# DC-PSx.net
KiCad netlist of a schematic drawn in EAGLE
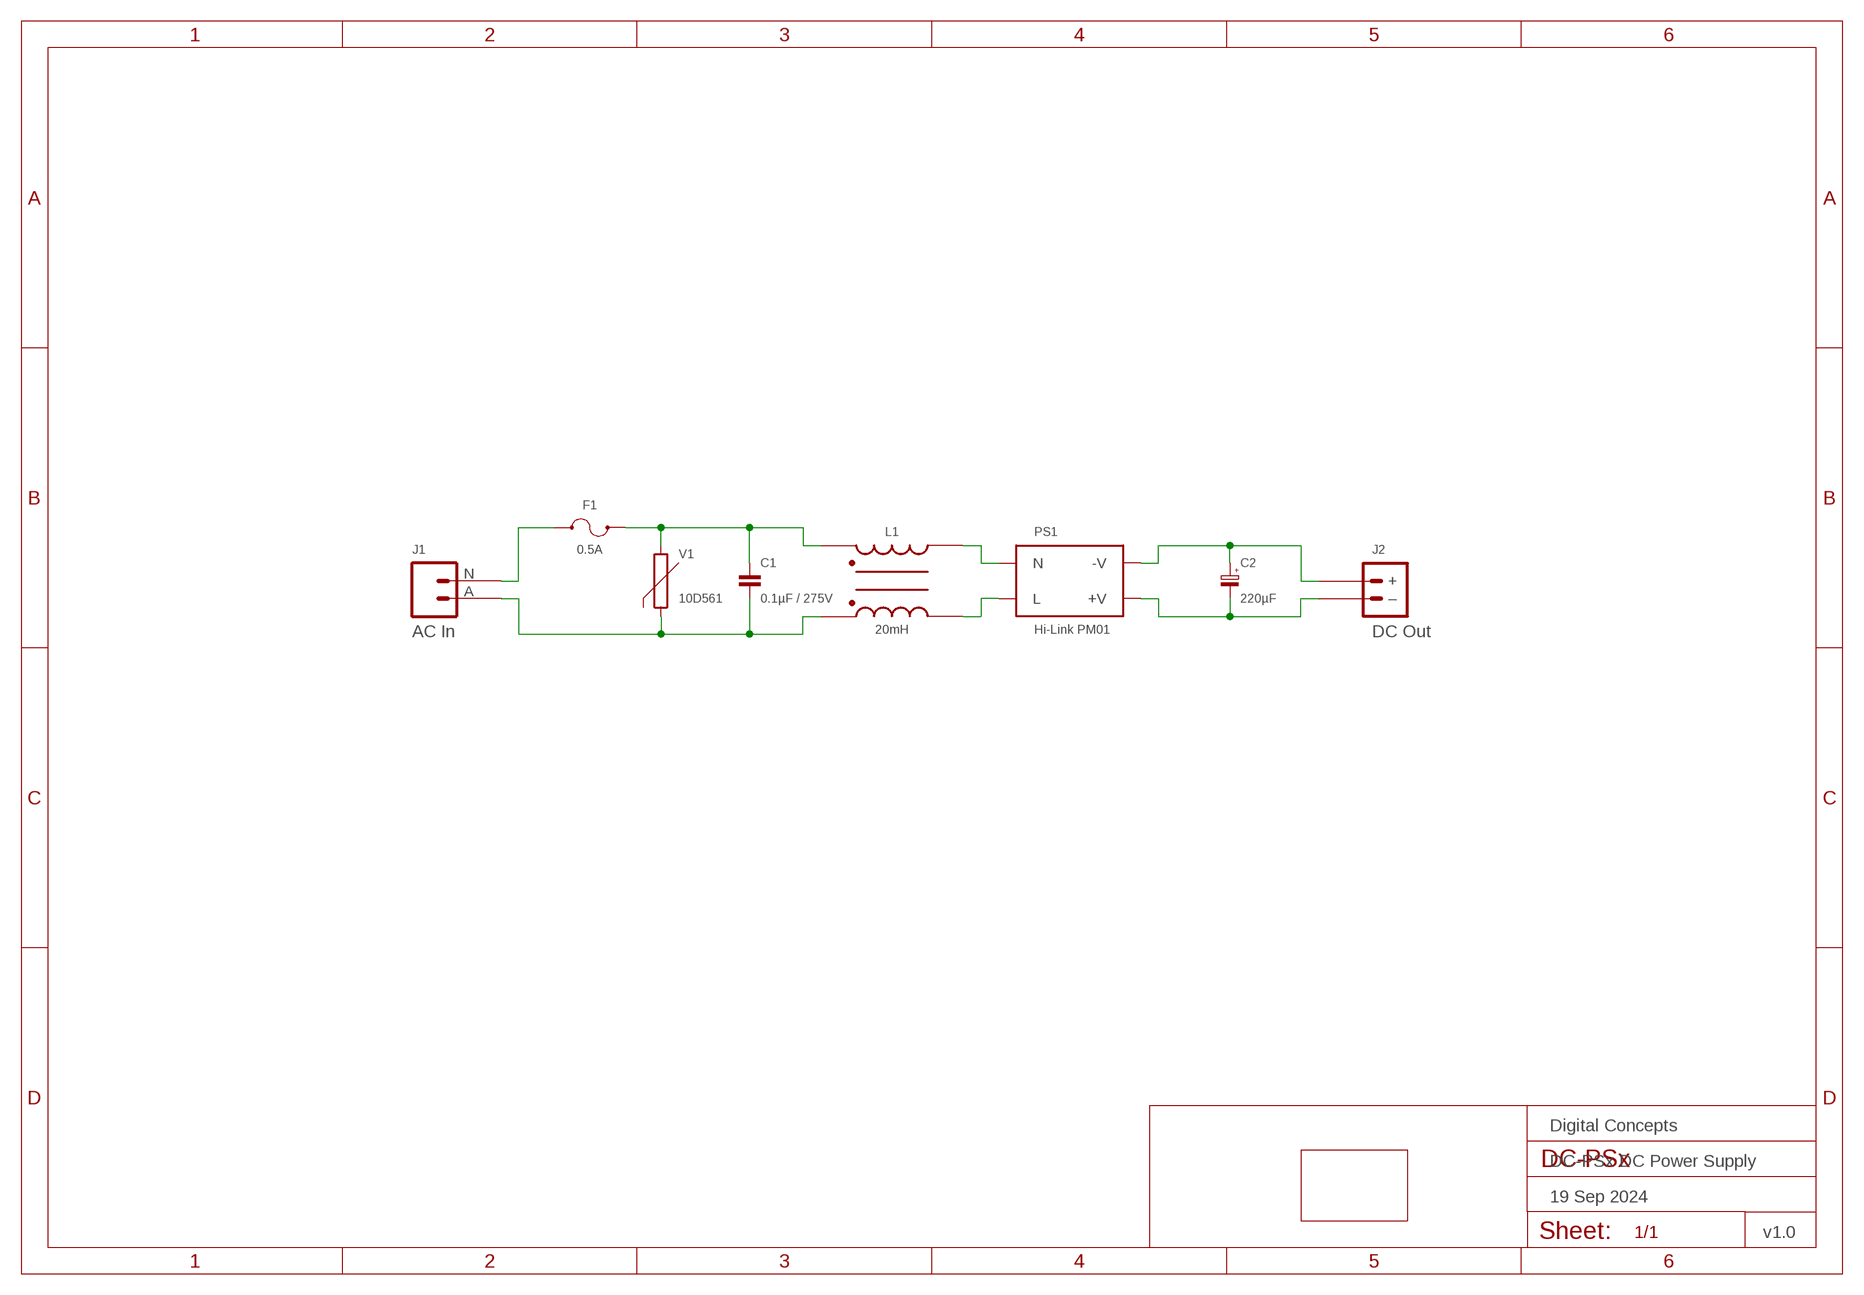
[diagram p0: schematic, sheet 1]

(export (version "E")
  (design (tool "Eeschema 10.0.6"))
  (components
    (comp (ref "C1")
      (value "0.1µF / 275V")
      (footprint "eagle-import:CAPACITOR-TENTA-SUPPRESSION")
      (libsource (lib "eagle-import") (part "CAPACITOR-TENTA-SUPPRESSION"))
    )
    (comp (ref "C2")
      (value "220µF")
      (footprint "eagle-import:E5-10,5")
      (libsource (lib "eagle-import") (part "CAPACITOR-ELECTROLYTICE5-10.5"))
    )
    (comp (ref "F1")
      (value "0.5A")
      (footprint "eagle-import:FUSE-HOLDER-1808")
      (libsource (lib "eagle-import") (part "FUSE-HOLDER-1808"))
    )
    (comp (ref "J1")
      (value "AC In")
      (footprint "eagle-import:DB-03_AC_POWER_SOCKET")
      (libsource (lib "eagle-import") (part "AC_POWER_SOCKET_DB-03"))
    )
    (comp (ref "J2")
      (value "DC Out")
      (footprint "eagle-import:JST-PH2.0-2-VERTICAL-POWER")
      (libsource (lib "eagle-import") (part "JST-PH2.0-2-VERTICAL-POWER"))
    )
    (comp (ref "L1")
      (value "20mH")
      (footprint "eagle-import:INDUCTOR-UU9.8")
      (libsource (lib "eagle-import") (part "INDUCTOR-COMMON-MODE-UU9.8"))
    )
    (comp (ref "PCB1")
      (value "PCB-OUTLINE-64X36")
      (footprint "eagle-import:PCB-POWER-SUPPLY-3")
      (libsource (lib "eagle-import") (part "PCB-OUTLINE-64X36"))
    )
    (comp (ref "PS1")
      (value "Hi-Link PM01")
      (footprint "eagle-import:HI-LINK_PM0X")
      (libsource (lib "eagle-import") (part "POWER_SUPPLY-HI-LINK"))
    )
    (comp (ref "V1")
      (value "10D561")
      (footprint "eagle-import:VARISTOR-10D561")
      (libsource (lib "eagle-import") (part "VARISTOR-10D561"))
    )
  )
  (nets
    (net (code "1") (name "Net-(C1-1)") (class "Default")
      (node (ref "C1") (pin "P$1") (pinfunction "1_P$1") (pintype "passive"))
      (node (ref "F1") (pin "P$2") (pinfunction "2_P$2") (pintype "passive"))
      (node (ref "L1") (pin "P$1") (pinfunction "1_P$1") (pintype "passive"))
      (node (ref "V1") (pin "2") (pinfunction "2_2") (pintype "passive"))
    )
    (net (code "2") (name "Net-(C1-2)") (class "Default")
      (node (ref "C1") (pin "P$2") (pinfunction "2_P$2") (pintype "passive"))
      (node (ref "J1") (pin "A") (pinfunction "2_A") (pintype "passive"))
      (node (ref "L1") (pin "P$4") (pinfunction "4_P$4") (pintype "passive"))
      (node (ref "V1") (pin "1") (pinfunction "1_1") (pintype "passive"))
    )
    (net (code "3") (name "Net-(F1-1)") (class "Default")
      (node (ref "F1") (pin "P$1") (pinfunction "1_P$1") (pintype "passive"))
      (node (ref "J1") (pin "N") (pinfunction "1_N") (pintype "passive"))
    )
    (net (code "4") (name "Net-(J2-–)") (class "Default")
      (node (ref "C2") (pin "-") (pinfunction "-_-") (pintype "passive"))
      (node (ref "J2") (pin "-") (pinfunction "–_-") (pintype "power_in"))
      (node (ref "PS1") (pin "+VO") (pinfunction "+V_+VO") (pintype "power_in"))
    )
    (net (code "5") (name "Net-(L1-2)") (class "Default")
      (node (ref "L1") (pin "P$2") (pinfunction "2_P$2") (pintype "passive"))
      (node (ref "PS1") (pin "AC-N") (pinfunction "N_AC-N") (pintype "power_in"))
    )
    (net (code "6") (name "Net-(L1-3)") (class "Default")
      (node (ref "L1") (pin "P$3") (pinfunction "3_P$3") (pintype "passive"))
      (node (ref "PS1") (pin "AC-L") (pinfunction "L_AC-L") (pintype "power_in"))
    )
    (net (code "7") (name "Net-(PS1--V)") (class "Default")
      (node (ref "C2") (pin "+") (pinfunction "+_+") (pintype "passive"))
      (node (ref "J2") (pin "+") (pinfunction "+_+") (pintype "power_in"))
      (node (ref "PS1") (pin "-VO") (pinfunction "-V_-VO") (pintype "power_in"))
    )
  )
)
